# controller.net
KiCad netlist of a schematic drawn in EAGLE
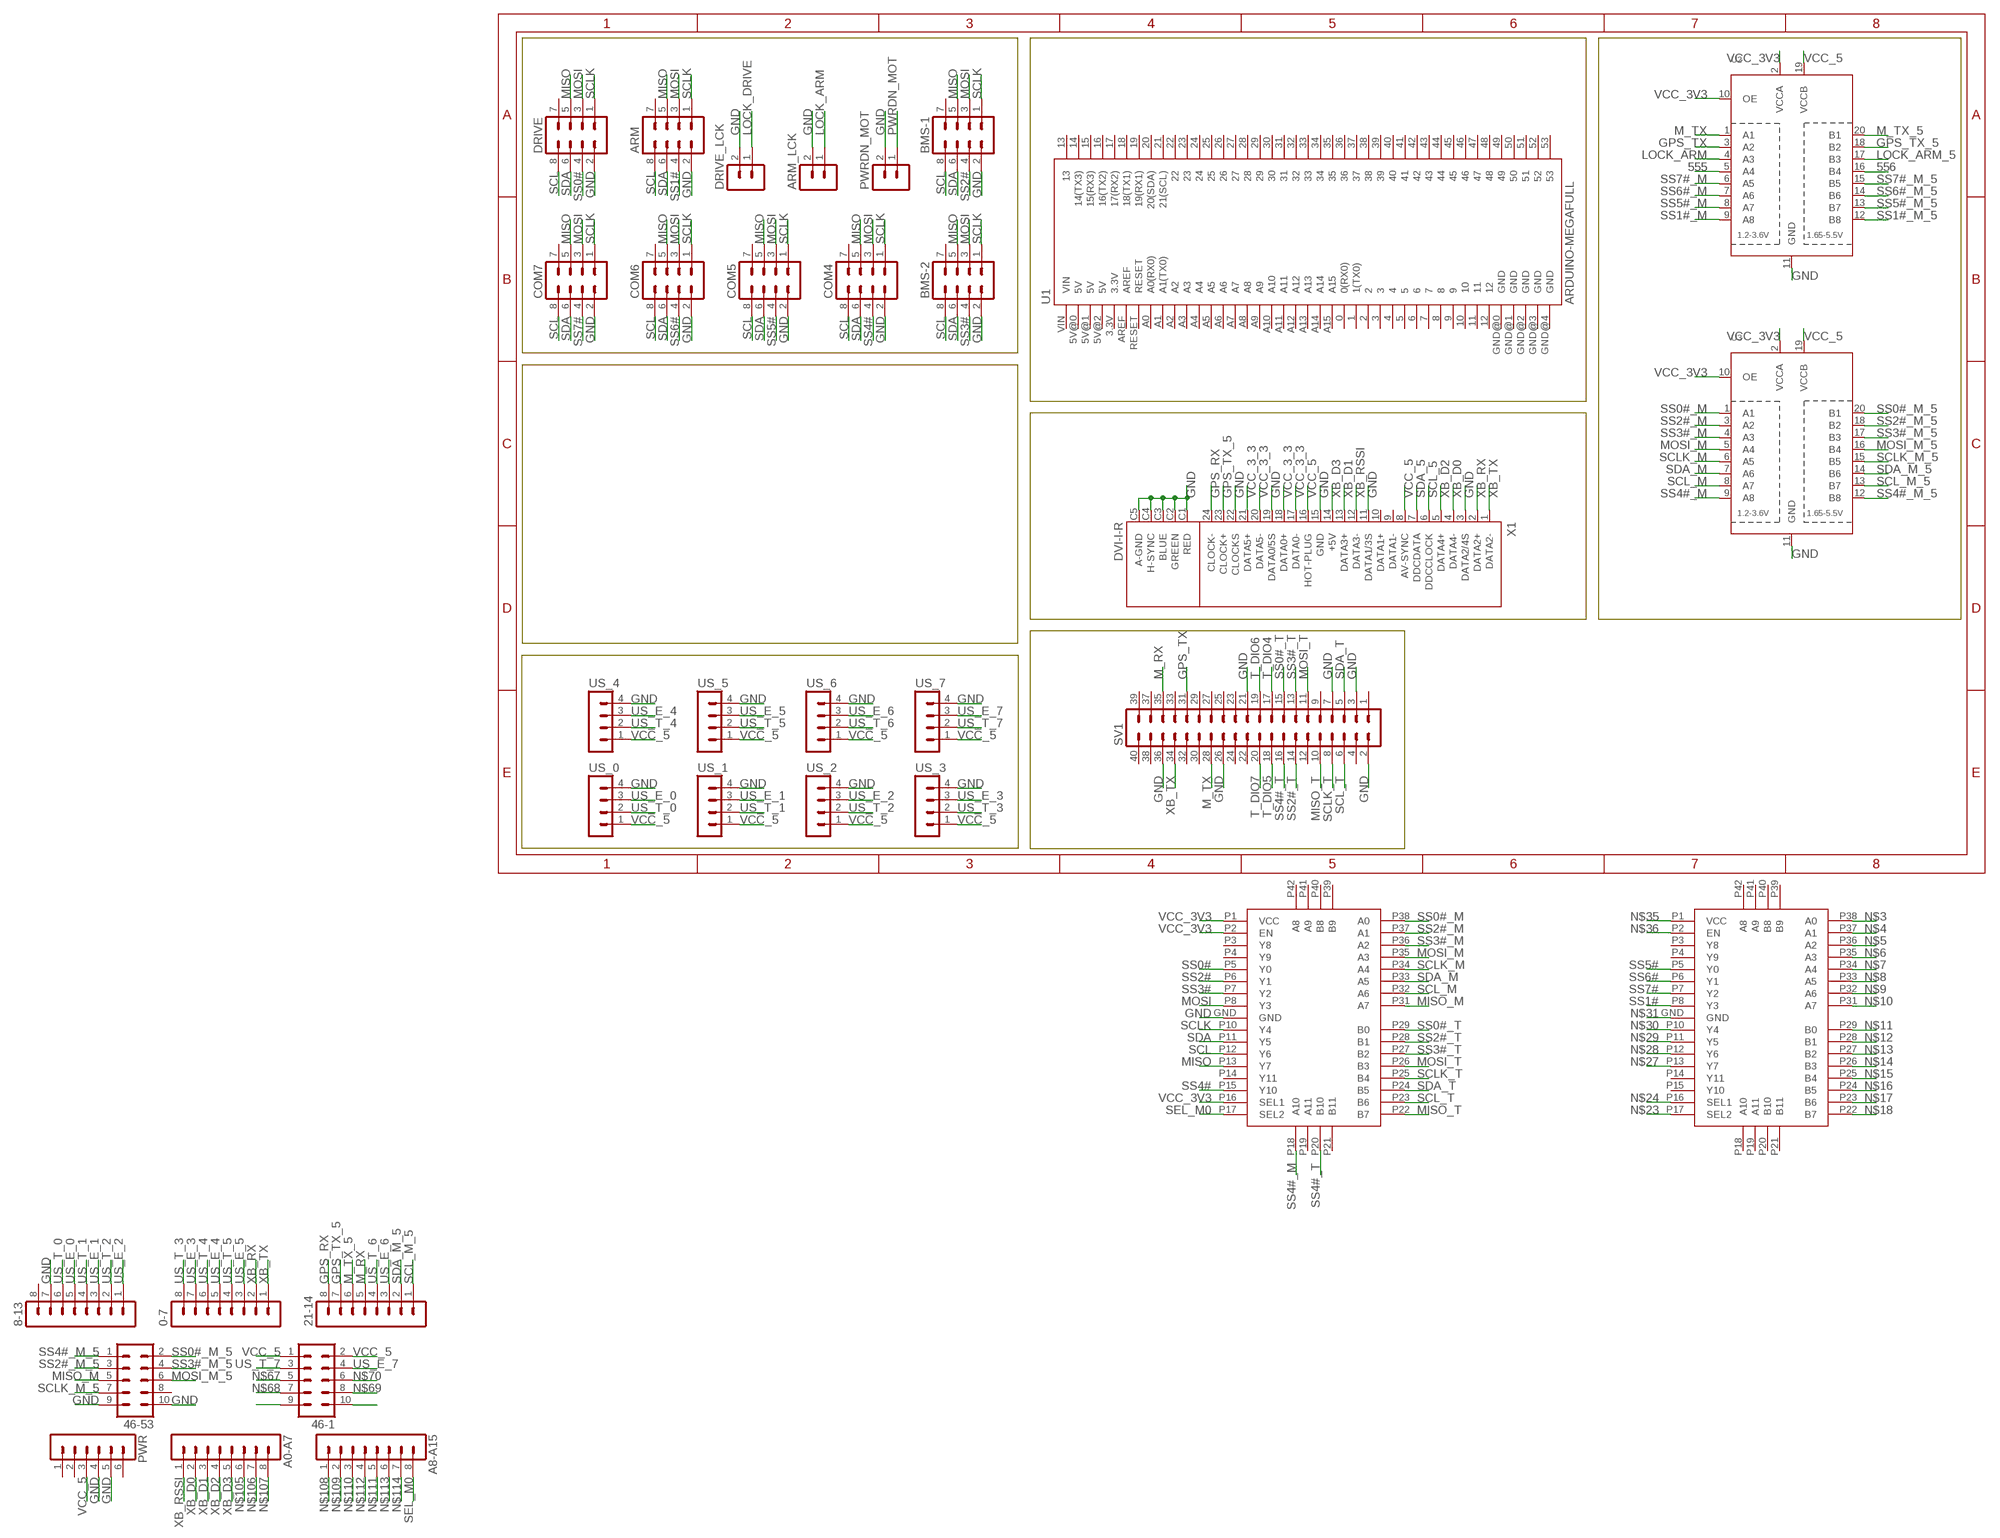
[diagram p0: schematic, sheet 1]

(export (version "E")
  (design (tool "Eeschema 10.0.6"))
  (components
    (comp (ref "0-7")
      (value "MA08-1")
      (footprint "eagle-import:MA08-1")
      (libsource (lib "eagle-import") (part "MA08-1"))
    )
    (comp (ref "8-13")
      (value "MA08-1")
      (footprint "eagle-import:MA08-1")
      (libsource (lib "eagle-import") (part "MA08-1"))
    )
    (comp (ref "21-14")
      (value "MA08-1")
      (footprint "eagle-import:MA08-1")
      (libsource (lib "eagle-import") (part "MA08-1"))
    )
    (comp (ref "46-1")
      (value "MA05-2")
      (footprint "eagle-import:MA05-2")
      (libsource (lib "eagle-import") (part "MA05-2"))
    )
    (comp (ref "46-53")
      (value "MA05-2")
      (footprint "eagle-import:MA05-2")
      (libsource (lib "eagle-import") (part "MA05-2"))
    )
    (comp (ref "A0-A7")
      (value "MA08-1")
      (footprint "eagle-import:MA08-1")
      (libsource (lib "eagle-import") (part "MA08-1"))
    )
    (comp (ref "A8-A15")
      (value "MA08-1")
      (footprint "eagle-import:MA08-1")
      (libsource (lib "eagle-import") (part "MA08-1"))
    )
    (comp (ref "ARM")
      (value "MA04-2")
      (footprint "eagle-import:MA04-2")
      (libsource (lib "eagle-import") (part "MA04-2"))
    )
    (comp (ref "ARM_LCK")
      (value "MA02-1")
      (footprint "eagle-import:MA02-1")
      (libsource (lib "eagle-import") (part "MA02-1"))
    )
    (comp (ref "BMS-1")
      (value "MA04-2")
      (footprint "eagle-import:MA04-2")
      (libsource (lib "eagle-import") (part "MA04-2"))
    )
    (comp (ref "BMS-2")
      (value "MA04-2")
      (footprint "eagle-import:MA04-2")
      (libsource (lib "eagle-import") (part "MA04-2"))
    )
    (comp (ref "COM4")
      (value "MA04-2")
      (footprint "eagle-import:MA04-2")
      (libsource (lib "eagle-import") (part "MA04-2"))
    )
    (comp (ref "COM5")
      (value "MA04-2")
      (footprint "eagle-import:MA04-2")
      (libsource (lib "eagle-import") (part "MA04-2"))
    )
    (comp (ref "COM6")
      (value "MA04-2")
      (footprint "eagle-import:MA04-2")
      (libsource (lib "eagle-import") (part "MA04-2"))
    )
    (comp (ref "COM7")
      (value "MA04-2")
      (footprint "eagle-import:MA04-2")
      (libsource (lib "eagle-import") (part "MA04-2"))
    )
    (comp (ref "DRIVE")
      (value "MA04-2")
      (footprint "eagle-import:MA04-2")
      (libsource (lib "eagle-import") (part "MA04-2"))
    )
    (comp (ref "DRIVE_LCK")
      (value "MA02-1")
      (footprint "eagle-import:MA02-1")
      (libsource (lib "eagle-import") (part "MA02-1"))
    )
    (comp (ref "PWR")
      (value "MA06-1")
      (footprint "eagle-import:MA06-1")
      (libsource (lib "eagle-import") (part "MA06-1"))
    )
    (comp (ref "PWRDN_MOT")
      (value "MA02-1")
      (footprint "eagle-import:MA02-1")
      (libsource (lib "eagle-import") (part "MA02-1"))
    )
    (comp (ref "SV1")
      (value "MA20-2")
      (footprint "eagle-import:MA20-2")
      (libsource (lib "eagle-import") (part "MA20-2"))
    )
    (comp (ref "U$5")
      (value "TS3DV642RUA")
      (footprint "eagle-import:R-PWQFN-N42")
      (libsource (lib "eagle-import") (part "TS3DV642RUA"))
    )
    (comp (ref "U$6")
      (value "TS3DV642RUA")
      (footprint "eagle-import:R-PWQFN-N42")
      (libsource (lib "eagle-import") (part "TS3DV642RUA"))
    )
    (comp (ref "U1")
      (value "ARDUINO-MEGAFULL")
      (footprint "eagle-import:ARDUINO_MEGA")
      (libsource (lib "eagle-import") (part "ARDUINO-MEGAFULL"))
    )
    (comp (ref "U2")
      (value "TXB0108PWR")
      (footprint "eagle-import:TSSOP20")
      (libsource (lib "eagle-import") (part "TXB0108PWR"))
    )
    (comp (ref "U3")
      (value "TXB0108PWR")
      (footprint "eagle-import:TSSOP20")
      (libsource (lib "eagle-import") (part "TXB0108PWR"))
    )
    (comp (ref "US_0")
      (value "MA04-1")
      (footprint "eagle-import:MA04-1")
      (libsource (lib "eagle-import") (part "MA04-1"))
    )
    (comp (ref "US_1")
      (value "MA04-1")
      (footprint "eagle-import:MA04-1")
      (libsource (lib "eagle-import") (part "MA04-1"))
    )
    (comp (ref "US_2")
      (value "MA04-1")
      (footprint "eagle-import:MA04-1")
      (libsource (lib "eagle-import") (part "MA04-1"))
    )
    (comp (ref "US_3")
      (value "MA04-1")
      (footprint "eagle-import:MA04-1")
      (libsource (lib "eagle-import") (part "MA04-1"))
    )
    (comp (ref "US_4")
      (value "MA04-1")
      (footprint "eagle-import:MA04-1")
      (libsource (lib "eagle-import") (part "MA04-1"))
    )
    (comp (ref "US_5")
      (value "MA04-1")
      (footprint "eagle-import:MA04-1")
      (libsource (lib "eagle-import") (part "MA04-1"))
    )
    (comp (ref "US_6")
      (value "MA04-1")
      (footprint "eagle-import:MA04-1")
      (libsource (lib "eagle-import") (part "MA04-1"))
    )
    (comp (ref "US_7")
      (value "MA04-1")
      (footprint "eagle-import:MA04-1")
      (libsource (lib "eagle-import") (part "MA04-1"))
    )
    (comp (ref "X1")
      (value "DVI-I-R")
      (footprint "eagle-import:DVI-I-R")
      (libsource (lib "eagle-import") (part "DVI-I-R"))
    )
  )
  (nets
    (net (code "1") (name "/555") (class "Default")
      (node (ref "U2") (pin "5") (pinfunction "A4_5") (pintype "bidirectional"))
    )
    (net (code "2") (name "/556") (class "Default")
      (node (ref "U2") (pin "16") (pinfunction "B4_16") (pintype "bidirectional"))
    )
    (net (code "3") (name "/GND") (class "Default")
      (node (ref "46-53") (pin "10") (pinfunction "10_10") (pintype "passive"))
      (node (ref "46-53") (pin "9") (pinfunction "9_9") (pintype "passive"))
      (node (ref "8-13") (pin "7") (pinfunction "7_7") (pintype "passive"))
      (node (ref "ARM") (pin "2") (pinfunction "2_2") (pintype "passive"))
      (node (ref "ARM_LCK") (pin "2") (pinfunction "2_2") (pintype "passive"))
      (node (ref "BMS-1") (pin "2") (pinfunction "2_2") (pintype "passive"))
      (node (ref "BMS-2") (pin "2") (pinfunction "2_2") (pintype "passive"))
      (node (ref "COM4") (pin "2") (pinfunction "2_2") (pintype "passive"))
      (node (ref "COM5") (pin "2") (pinfunction "2_2") (pintype "passive"))
      (node (ref "COM6") (pin "2") (pinfunction "2_2") (pintype "passive"))
      (node (ref "COM7") (pin "2") (pinfunction "2_2") (pintype "passive"))
      (node (ref "DRIVE") (pin "2") (pinfunction "2_2") (pintype "passive"))
      (node (ref "DRIVE_LCK") (pin "2") (pinfunction "2_2") (pintype "passive"))
      (node (ref "PWR") (pin "4") (pinfunction "4_4") (pintype "passive"))
      (node (ref "PWR") (pin "5") (pinfunction "5_5") (pintype "passive"))
      (node (ref "PWRDN_MOT") (pin "2") (pinfunction "2_2") (pintype "passive"))
      (node (ref "SV1") (pin "2") (pinfunction "2_2") (pintype "passive"))
      (node (ref "SV1") (pin "21") (pinfunction "21_21") (pintype "passive"))
      (node (ref "SV1") (pin "26") (pinfunction "26_26") (pintype "passive"))
      (node (ref "SV1") (pin "3") (pinfunction "3_3") (pintype "passive"))
      (node (ref "SV1") (pin "36") (pinfunction "36_36") (pintype "passive"))
      (node (ref "SV1") (pin "7") (pinfunction "7_7") (pintype "passive"))
      (node (ref "U$5") (pin "GND") (pinfunction "GND_GND") (pintype "bidirectional"))
      (node (ref "U2") (pin "11") (pinfunction "GND_11") (pintype "bidirectional"))
      (node (ref "U3") (pin "11") (pinfunction "GND_11") (pintype "bidirectional"))
      (node (ref "US_0") (pin "4") (pinfunction "4_4") (pintype "passive"))
      (node (ref "US_1") (pin "4") (pinfunction "4_4") (pintype "passive"))
      (node (ref "US_2") (pin "4") (pinfunction "4_4") (pintype "passive"))
      (node (ref "US_3") (pin "4") (pinfunction "4_4") (pintype "passive"))
      (node (ref "US_4") (pin "4") (pinfunction "4_4") (pintype "passive"))
      (node (ref "US_5") (pin "4") (pinfunction "4_4") (pintype "passive"))
      (node (ref "US_6") (pin "4") (pinfunction "4_4") (pintype "passive"))
      (node (ref "US_7") (pin "4") (pinfunction "4_4") (pintype "passive"))
      (node (ref "X1") (pin "11") (pinfunction "DATA1/3S_11") (pintype "passive"))
      (node (ref "X1") (pin "15") (pinfunction "GND_15") (pintype "power_in"))
      (node (ref "X1") (pin "19") (pinfunction "DATA0/5S_19") (pintype "passive"))
      (node (ref "X1") (pin "22") (pinfunction "CLOCKS_22") (pintype "passive"))
      (node (ref "X1") (pin "3") (pinfunction "DATA2/4S_3") (pintype "passive"))
      (node (ref "X1") (pin "C1") (pinfunction "RED_C1") (pintype "passive"))
      (node (ref "X1") (pin "C2") (pinfunction "GREEN_C2") (pintype "passive"))
      (node (ref "X1") (pin "C3") (pinfunction "BLUE_C3") (pintype "passive"))
      (node (ref "X1") (pin "C4") (pinfunction "H-SYNC_C4") (pintype "passive"))
      (node (ref "X1") (pin "C5") (pinfunction "A-GND_C5") (pintype "power_in"))
    )
    (net (code "4") (name "/GPS_RX") (class "Default")
      (node (ref "21-14") (pin "8") (pinfunction "8_8") (pintype "passive"))
      (node (ref "X1") (pin "24") (pinfunction "CLOCK-_24") (pintype "passive"))
    )
    (net (code "5") (name "/GPS_TX") (class "Default")
      (node (ref "SV1") (pin "31") (pinfunction "31_31") (pintype "passive"))
      (node (ref "U2") (pin "3") (pinfunction "A2_3") (pintype "bidirectional"))
    )
    (net (code "6") (name "/GPS_TX_5") (class "Default")
      (node (ref "21-14") (pin "7") (pinfunction "7_7") (pintype "passive"))
      (node (ref "U2") (pin "18") (pinfunction "B2_18") (pintype "bidirectional"))
      (node (ref "X1") (pin "23") (pinfunction "CLOCK+_23") (pintype "passive"))
    )
    (net (code "7") (name "/LOCK_ARM") (class "Default")
      (node (ref "ARM_LCK") (pin "1") (pinfunction "1_1") (pintype "passive"))
      (node (ref "U2") (pin "4") (pinfunction "A3_4") (pintype "bidirectional"))
    )
    (net (code "8") (name "/LOCK_ARM_5") (class "Default")
      (node (ref "U2") (pin "17") (pinfunction "B3_17") (pintype "bidirectional"))
    )
    (net (code "9") (name "/LOCK_DRIVE") (class "Default")
      (node (ref "DRIVE_LCK") (pin "1") (pinfunction "1_1") (pintype "passive"))
    )
    (net (code "10") (name "/MISO") (class "Default")
      (node (ref "ARM") (pin "5") (pinfunction "5_5") (pintype "passive"))
      (node (ref "BMS-1") (pin "5") (pinfunction "5_5") (pintype "passive"))
      (node (ref "BMS-2") (pin "5") (pinfunction "5_5") (pintype "passive"))
      (node (ref "COM4") (pin "5") (pinfunction "5_5") (pintype "passive"))
      (node (ref "COM5") (pin "5") (pinfunction "5_5") (pintype "passive"))
      (node (ref "COM6") (pin "5") (pinfunction "5_5") (pintype "passive"))
      (node (ref "COM7") (pin "5") (pinfunction "5_5") (pintype "passive"))
      (node (ref "DRIVE") (pin "5") (pinfunction "5_5") (pintype "passive"))
      (node (ref "U$5") (pin "P13") (pinfunction "Y7_P13") (pintype "bidirectional"))
    )
    (net (code "11") (name "/MISO_M") (class "Default")
      (node (ref "46-53") (pin "5") (pinfunction "5_5") (pintype "passive"))
      (node (ref "U$5") (pin "P31") (pinfunction "A7_P31") (pintype "bidirectional"))
    )
    (net (code "12") (name "/MISO_T") (class "Default")
      (node (ref "SV1") (pin "10") (pinfunction "10_10") (pintype "passive"))
      (node (ref "U$5") (pin "P22") (pinfunction "B7_P22") (pintype "bidirectional"))
    )
    (net (code "13") (name "/MOSI") (class "Default")
      (node (ref "ARM") (pin "3") (pinfunction "3_3") (pintype "passive"))
      (node (ref "BMS-1") (pin "3") (pinfunction "3_3") (pintype "passive"))
      (node (ref "BMS-2") (pin "3") (pinfunction "3_3") (pintype "passive"))
      (node (ref "COM4") (pin "3") (pinfunction "3_3") (pintype "passive"))
      (node (ref "COM5") (pin "3") (pinfunction "3_3") (pintype "passive"))
      (node (ref "COM6") (pin "3") (pinfunction "3_3") (pintype "passive"))
      (node (ref "COM7") (pin "3") (pinfunction "3_3") (pintype "passive"))
      (node (ref "DRIVE") (pin "3") (pinfunction "3_3") (pintype "passive"))
      (node (ref "U$5") (pin "P8") (pinfunction "Y3_P8") (pintype "bidirectional"))
    )
    (net (code "14") (name "/MOSI_M") (class "Default")
      (node (ref "U$5") (pin "P35") (pinfunction "A3_P35") (pintype "bidirectional"))
      (node (ref "U3") (pin "5") (pinfunction "A4_5") (pintype "bidirectional"))
    )
    (net (code "15") (name "/MOSI_M_5") (class "Default")
      (node (ref "46-53") (pin "6") (pinfunction "6_6") (pintype "passive"))
      (node (ref "U3") (pin "16") (pinfunction "B4_16") (pintype "bidirectional"))
    )
    (net (code "16") (name "/MOSI_T") (class "Default")
      (node (ref "SV1") (pin "11") (pinfunction "11_11") (pintype "passive"))
      (node (ref "U$5") (pin "P26") (pinfunction "B3_P26") (pintype "bidirectional"))
    )
    (net (code "17") (name "/M_RX") (class "Default")
      (node (ref "21-14") (pin "5") (pinfunction "5_5") (pintype "passive"))
      (node (ref "SV1") (pin "35") (pinfunction "35_35") (pintype "passive"))
    )
    (net (code "18") (name "/M_TX") (class "Default")
      (node (ref "SV1") (pin "28") (pinfunction "28_28") (pintype "passive"))
      (node (ref "U2") (pin "1") (pinfunction "A1_1") (pintype "bidirectional"))
    )
    (net (code "19") (name "/M_TX_5") (class "Default")
      (node (ref "21-14") (pin "6") (pinfunction "6_6") (pintype "passive"))
      (node (ref "U2") (pin "20") (pinfunction "B1_20") (pintype "bidirectional"))
    )
    (net (code "20") (name "/N$3") (class "Default")
      (node (ref "U$6") (pin "P38") (pinfunction "A0_P38") (pintype "bidirectional"))
    )
    (net (code "21") (name "/N$4") (class "Default")
      (node (ref "U$6") (pin "P37") (pinfunction "A1_P37") (pintype "bidirectional"))
    )
    (net (code "22") (name "/N$5") (class "Default")
      (node (ref "U$6") (pin "P36") (pinfunction "A2_P36") (pintype "bidirectional"))
    )
    (net (code "23") (name "/N$6") (class "Default")
      (node (ref "U$6") (pin "P35") (pinfunction "A3_P35") (pintype "bidirectional"))
    )
    (net (code "24") (name "/N$7") (class "Default")
      (node (ref "U$6") (pin "P34") (pinfunction "A4_P34") (pintype "bidirectional"))
    )
    (net (code "25") (name "/N$8") (class "Default")
      (node (ref "U$6") (pin "P33") (pinfunction "A5_P33") (pintype "bidirectional"))
    )
    (net (code "26") (name "/N$9") (class "Default")
      (node (ref "U$6") (pin "P32") (pinfunction "A6_P32") (pintype "bidirectional"))
    )
    (net (code "27") (name "/N$10") (class "Default")
      (node (ref "U$6") (pin "P31") (pinfunction "A7_P31") (pintype "bidirectional"))
    )
    (net (code "28") (name "/N$11") (class "Default")
      (node (ref "U$6") (pin "P29") (pinfunction "B0_P29") (pintype "bidirectional"))
    )
    (net (code "29") (name "/N$12") (class "Default")
      (node (ref "U$6") (pin "P28") (pinfunction "B1_P28") (pintype "bidirectional"))
    )
    (net (code "30") (name "/N$13") (class "Default")
      (node (ref "U$6") (pin "P27") (pinfunction "B2_P27") (pintype "bidirectional"))
    )
    (net (code "31") (name "/N$14") (class "Default")
      (node (ref "U$6") (pin "P26") (pinfunction "B3_P26") (pintype "bidirectional"))
    )
    (net (code "32") (name "/N$15") (class "Default")
      (node (ref "U$6") (pin "P25") (pinfunction "B4_P25") (pintype "bidirectional"))
    )
    (net (code "33") (name "/N$16") (class "Default")
      (node (ref "U$6") (pin "P24") (pinfunction "B5_P24") (pintype "bidirectional"))
    )
    (net (code "34") (name "/N$17") (class "Default")
      (node (ref "U$6") (pin "P23") (pinfunction "B6_P23") (pintype "bidirectional"))
    )
    (net (code "35") (name "/N$18") (class "Default")
      (node (ref "U$6") (pin "P22") (pinfunction "B7_P22") (pintype "bidirectional"))
    )
    (net (code "36") (name "/N$23") (class "Default")
      (node (ref "U$6") (pin "P17") (pinfunction "SEL2_P17") (pintype "bidirectional"))
    )
    (net (code "37") (name "/N$24") (class "Default")
      (node (ref "U$6") (pin "P16") (pinfunction "SEL1_P16") (pintype "bidirectional"))
    )
    (net (code "38") (name "/N$27") (class "Default")
      (node (ref "U$6") (pin "P13") (pinfunction "Y7_P13") (pintype "bidirectional"))
    )
    (net (code "39") (name "/N$28") (class "Default")
      (node (ref "U$6") (pin "P12") (pinfunction "Y6_P12") (pintype "bidirectional"))
    )
    (net (code "40") (name "/N$29") (class "Default")
      (node (ref "U$6") (pin "P11") (pinfunction "Y5_P11") (pintype "bidirectional"))
    )
    (net (code "41") (name "/N$30") (class "Default")
      (node (ref "U$6") (pin "P10") (pinfunction "Y4_P10") (pintype "bidirectional"))
    )
    (net (code "42") (name "/N$31") (class "Default")
      (node (ref "U$6") (pin "GND") (pinfunction "GND_GND") (pintype "bidirectional"))
    )
    (net (code "43") (name "/N$35") (class "Default")
      (node (ref "U$6") (pin "P1") (pinfunction "VCC_P1") (pintype "bidirectional"))
    )
    (net (code "44") (name "/N$36") (class "Default")
      (node (ref "U$6") (pin "P2") (pinfunction "EN_P2") (pintype "bidirectional"))
    )
    (net (code "45") (name "/N$67") (class "Default")
      (node (ref "46-1") (pin "5") (pinfunction "5_5") (pintype "passive"))
    )
    (net (code "46") (name "/N$68") (class "Default")
      (node (ref "46-1") (pin "7") (pinfunction "7_7") (pintype "passive"))
    )
    (net (code "47") (name "/N$69") (class "Default")
      (node (ref "46-1") (pin "8") (pinfunction "8_8") (pintype "passive"))
    )
    (net (code "48") (name "/N$70") (class "Default")
      (node (ref "46-1") (pin "6") (pinfunction "6_6") (pintype "passive"))
    )
    (net (code "49") (name "/N$105") (class "Default")
      (node (ref "A0-A7") (pin "6") (pinfunction "6_6") (pintype "passive"))
    )
    (net (code "50") (name "/N$106") (class "Default")
      (node (ref "A0-A7") (pin "7") (pinfunction "7_7") (pintype "passive"))
    )
    (net (code "51") (name "/N$107") (class "Default")
      (node (ref "A0-A7") (pin "8") (pinfunction "8_8") (pintype "passive"))
    )
    (net (code "52") (name "/N$108") (class "Default")
      (node (ref "A8-A15") (pin "1") (pinfunction "1_1") (pintype "passive"))
    )
    (net (code "53") (name "/N$109") (class "Default")
      (node (ref "A8-A15") (pin "2") (pinfunction "2_2") (pintype "passive"))
    )
    (net (code "54") (name "/N$110") (class "Default")
      (node (ref "A8-A15") (pin "3") (pinfunction "3_3") (pintype "passive"))
    )
    (net (code "55") (name "/N$111") (class "Default")
      (node (ref "A8-A15") (pin "5") (pinfunction "5_5") (pintype "passive"))
    )
    (net (code "56") (name "/N$112") (class "Default")
      (node (ref "A8-A15") (pin "4") (pinfunction "4_4") (pintype "passive"))
    )
    (net (code "57") (name "/N$113") (class "Default")
      (node (ref "A8-A15") (pin "6") (pinfunction "6_6") (pintype "passive"))
    )
    (net (code "58") (name "/N$114") (class "Default")
      (node (ref "A8-A15") (pin "7") (pinfunction "7_7") (pintype "passive"))
    )
    (net (code "59") (name "/PWRDN_MOT") (class "Default")
      (node (ref "PWRDN_MOT") (pin "1") (pinfunction "1_1") (pintype "passive"))
    )
    (net (code "60") (name "/SCL") (class "Default")
      (node (ref "ARM") (pin "8") (pinfunction "8_8") (pintype "passive"))
      (node (ref "BMS-1") (pin "8") (pinfunction "8_8") (pintype "passive"))
      (node (ref "BMS-2") (pin "8") (pinfunction "8_8") (pintype "passive"))
      (node (ref "COM4") (pin "8") (pinfunction "8_8") (pintype "passive"))
      (node (ref "COM5") (pin "8") (pinfunction "8_8") (pintype "passive"))
      (node (ref "COM6") (pin "8") (pinfunction "8_8") (pintype "passive"))
      (node (ref "COM7") (pin "8") (pinfunction "8_8") (pintype "passive"))
      (node (ref "DRIVE") (pin "8") (pinfunction "8_8") (pintype "passive"))
      (node (ref "U$5") (pin "P12") (pinfunction "Y6_P12") (pintype "bidirectional"))
    )
    (net (code "61") (name "/SCLK") (class "Default")
      (node (ref "ARM") (pin "1") (pinfunction "1_1") (pintype "passive"))
      (node (ref "BMS-1") (pin "1") (pinfunction "1_1") (pintype "passive"))
      (node (ref "BMS-2") (pin "1") (pinfunction "1_1") (pintype "passive"))
      (node (ref "COM4") (pin "1") (pinfunction "1_1") (pintype "passive"))
      (node (ref "COM5") (pin "1") (pinfunction "1_1") (pintype "passive"))
      (node (ref "COM6") (pin "1") (pinfunction "1_1") (pintype "passive"))
      (node (ref "COM7") (pin "1") (pinfunction "1_1") (pintype "passive"))
      (node (ref "DRIVE") (pin "1") (pinfunction "1_1") (pintype "passive"))
      (node (ref "U$5") (pin "P10") (pinfunction "Y4_P10") (pintype "bidirectional"))
    )
    (net (code "62") (name "/SCLK_M") (class "Default")
      (node (ref "U$5") (pin "P34") (pinfunction "A4_P34") (pintype "bidirectional"))
      (node (ref "U3") (pin "6") (pinfunction "A5_6") (pintype "bidirectional"))
    )
    (net (code "63") (name "/SCLK_M_5") (class "Default")
      (node (ref "46-53") (pin "7") (pinfunction "7_7") (pintype "passive"))
      (node (ref "U3") (pin "15") (pinfunction "B5_15") (pintype "bidirectional"))
    )
    (net (code "64") (name "/SCLK_T") (class "Default")
      (node (ref "SV1") (pin "8") (pinfunction "8_8") (pintype "passive"))
      (node (ref "U$5") (pin "P25") (pinfunction "B4_P25") (pintype "bidirectional"))
    )
    (net (code "65") (name "/SCL_5") (class "Default")
      (node (ref "X1") (pin "6") (pinfunction "DDCCLOCK_6") (pintype "passive"))
    )
    (net (code "66") (name "/SCL_M") (class "Default")
      (node (ref "U$5") (pin "P32") (pinfunction "A6_P32") (pintype "bidirectional"))
      (node (ref "U3") (pin "8") (pinfunction "A7_8") (pintype "bidirectional"))
    )
    (net (code "67") (name "/SCL_M_5") (class "Default")
      (node (ref "21-14") (pin "1") (pinfunction "1_1") (pintype "passive"))
      (node (ref "U3") (pin "13") (pinfunction "B7_13") (pintype "bidirectional"))
    )
    (net (code "68") (name "/SCL_T") (class "Default")
      (node (ref "SV1") (pin "6") (pinfunction "6_6") (pintype "passive"))
      (node (ref "U$5") (pin "P23") (pinfunction "B6_P23") (pintype "bidirectional"))
    )
    (net (code "69") (name "/SDA") (class "Default")
      (node (ref "ARM") (pin "6") (pinfunction "6_6") (pintype "passive"))
      (node (ref "BMS-1") (pin "6") (pinfunction "6_6") (pintype "passive"))
      (node (ref "BMS-2") (pin "6") (pinfunction "6_6") (pintype "passive"))
      (node (ref "COM4") (pin "6") (pinfunction "6_6") (pintype "passive"))
      (node (ref "COM5") (pin "6") (pinfunction "6_6") (pintype "passive"))
      (node (ref "COM6") (pin "6") (pinfunction "6_6") (pintype "passive"))
      (node (ref "COM7") (pin "6") (pinfunction "6_6") (pintype "passive"))
      (node (ref "DRIVE") (pin "6") (pinfunction "6_6") (pintype "passive"))
      (node (ref "U$5") (pin "P11") (pinfunction "Y5_P11") (pintype "bidirectional"))
    )
    (net (code "70") (name "/SDA_5") (class "Default")
      (node (ref "X1") (pin "7") (pinfunction "DDCDATA_7") (pintype "passive"))
    )
    (net (code "71") (name "/SDA_M") (class "Default")
      (node (ref "U$5") (pin "P33") (pinfunction "A5_P33") (pintype "bidirectional"))
      (node (ref "U3") (pin "7") (pinfunction "A6_7") (pintype "bidirectional"))
    )
    (net (code "72") (name "/SDA_M_5") (class "Default")
      (node (ref "21-14") (pin "2") (pinfunction "2_2") (pintype "passive"))
      (node (ref "U3") (pin "14") (pinfunction "B6_14") (pintype "bidirectional"))
    )
    (net (code "73") (name "/SDA_T") (class "Default")
      (node (ref "SV1") (pin "5") (pinfunction "5_5") (pintype "passive"))
      (node (ref "U$5") (pin "P24") (pinfunction "B5_P24") (pintype "bidirectional"))
    )
    (net (code "74") (name "/SEL_M0") (class "Default")
      (node (ref "A8-A15") (pin "8") (pinfunction "8_8") (pintype "passive"))
      (node (ref "U$5") (pin "P17") (pinfunction "SEL2_P17") (pintype "bidirectional"))
    )
    (net (code "75") (name "/SS0#") (class "Default")
      (node (ref "DRIVE") (pin "4") (pinfunction "4_4") (pintype "passive"))
      (node (ref "U$5") (pin "P5") (pinfunction "Y0_P5") (pintype "bidirectional"))
    )
    (net (code "76") (name "/SS0#_M") (class "Default")
      (node (ref "U$5") (pin "P38") (pinfunction "A0_P38") (pintype "bidirectional"))
      (node (ref "U3") (pin "1") (pinfunction "A1_1") (pintype "bidirectional"))
    )
    (net (code "77") (name "/SS0#_M_5") (class "Default")
      (node (ref "46-53") (pin "2") (pinfunction "2_2") (pintype "passive"))
      (node (ref "U3") (pin "20") (pinfunction "B1_20") (pintype "bidirectional"))
    )
    (net (code "78") (name "/SS0#_T") (class "Default")
      (node (ref "SV1") (pin "15") (pinfunction "15_15") (pintype "passive"))
      (node (ref "U$5") (pin "P29") (pinfunction "B0_P29") (pintype "bidirectional"))
    )
    (net (code "79") (name "/SS1#") (class "Default")
      (node (ref "ARM") (pin "4") (pinfunction "4_4") (pintype "passive"))
      (node (ref "U$6") (pin "P8") (pinfunction "Y3_P8") (pintype "bidirectional"))
    )
    (net (code "80") (name "/SS1#_M") (class "Default")
      (node (ref "U2") (pin "9") (pinfunction "A8_9") (pintype "bidirectional"))
    )
    (net (code "81") (name "/SS1#_M_5") (class "Default")
      (node (ref "U2") (pin "12") (pinfunction "B8_12") (pintype "bidirectional"))
    )
    (net (code "82") (name "/SS2#") (class "Default")
      (node (ref "BMS-1") (pin "4") (pinfunction "4_4") (pintype "passive"))
      (node (ref "U$5") (pin "P6") (pinfunction "Y1_P6") (pintype "bidirectional"))
    )
    (net (code "83") (name "/SS2#_M") (class "Default")
      (node (ref "U$5") (pin "P37") (pinfunction "A1_P37") (pintype "bidirectional"))
      (node (ref "U3") (pin "3") (pinfunction "A2_3") (pintype "bidirectional"))
    )
    (net (code "84") (name "/SS2#_M_5") (class "Default")
      (node (ref "46-53") (pin "3") (pinfunction "3_3") (pintype "passive"))
      (node (ref "U3") (pin "18") (pinfunction "B2_18") (pintype "bidirectional"))
    )
    (net (code "85") (name "/SS2#_T") (class "Default")
      (node (ref "SV1") (pin "14") (pinfunction "14_14") (pintype "passive"))
      (node (ref "U$5") (pin "P28") (pinfunction "B1_P28") (pintype "bidirectional"))
    )
    (net (code "86") (name "/SS3#") (class "Default")
      (node (ref "BMS-2") (pin "4") (pinfunction "4_4") (pintype "passive"))
      (node (ref "U$5") (pin "P7") (pinfunction "Y2_P7") (pintype "bidirectional"))
    )
    (net (code "87") (name "/SS3#_M") (class "Default")
      (node (ref "U$5") (pin "P36") (pinfunction "A2_P36") (pintype "bidirectional"))
      (node (ref "U3") (pin "4") (pinfunction "A3_4") (pintype "bidirectional"))
    )
    (net (code "88") (name "/SS3#_M_5") (class "Default")
      (node (ref "46-53") (pin "4") (pinfunction "4_4") (pintype "passive"))
      (node (ref "U3") (pin "17") (pinfunction "B3_17") (pintype "bidirectional"))
    )
    (net (code "89") (name "/SS3#_T") (class "Default")
      (node (ref "SV1") (pin "13") (pinfunction "13_13") (pintype "passive"))
      (node (ref "U$5") (pin "P27") (pinfunction "B2_P27") (pintype "bidirectional"))
    )
    (net (code "90") (name "/SS4#") (class "Default")
      (node (ref "COM4") (pin "4") (pinfunction "4_4") (pintype "passive"))
      (node (ref "U$5") (pin "P15") (pinfunction "Y10_P15") (pintype "bidirectional"))
    )
    (net (code "91") (name "/SS4#_M") (class "Default")
      (node (ref "U$5") (pin "P18") (pinfunction "A10_P18") (pintype "bidirectional"))
      (node (ref "U3") (pin "9") (pinfunction "A8_9") (pintype "bidirectional"))
    )
    (net (code "92") (name "/SS4#_M_5") (class "Default")
      (node (ref "46-53") (pin "1") (pinfunction "1_1") (pintype "passive"))
      (node (ref "U3") (pin "12") (pinfunction "B8_12") (pintype "bidirectional"))
    )
    (net (code "93") (name "/SS4#_T") (class "Default")
      (node (ref "SV1") (pin "16") (pinfunction "16_16") (pintype "passive"))
      (node (ref "U$5") (pin "P20") (pinfunction "B10_P20") (pintype "bidirectional"))
    )
    (net (code "94") (name "/SS5#") (class "Default")
      (node (ref "COM5") (pin "4") (pinfunction "4_4") (pintype "passive"))
      (node (ref "U$6") (pin "P5") (pinfunction "Y0_P5") (pintype "bidirectional"))
    )
    (net (code "95") (name "/SS5#_M") (class "Default")
      (node (ref "U2") (pin "8") (pinfunction "A7_8") (pintype "bidirectional"))
    )
    (net (code "96") (name "/SS5#_M_5") (class "Default")
      (node (ref "U2") (pin "13") (pinfunction "B7_13") (pintype "bidirectional"))
    )
    (net (code "97") (name "/SS6#") (class "Default")
      (node (ref "COM6") (pin "4") (pinfunction "4_4") (pintype "passive"))
      (node (ref "U$6") (pin "P6") (pinfunction "Y1_P6") (pintype "bidirectional"))
    )
    (net (code "98") (name "/SS6#_M") (class "Default")
      (node (ref "U2") (pin "7") (pinfunction "A6_7") (pintype "bidirectional"))
    )
    (net (code "99") (name "/SS6#_M_5") (class "Default")
      (node (ref "U2") (pin "14") (pinfunction "B6_14") (pintype "bidirectional"))
    )
    (net (code "100") (name "/SS7#") (class "Default")
      (node (ref "COM7") (pin "4") (pinfunction "4_4") (pintype "passive"))
      (node (ref "U$6") (pin "P7") (pinfunction "Y2_P7") (pintype "bidirectional"))
    )
    (net (code "101") (name "/SS7#_M") (class "Default")
      (node (ref "U2") (pin "6") (pinfunction "A5_6") (pintype "bidirectional"))
    )
    (net (code "102") (name "/SS7#_M_5") (class "Default")
      (node (ref "U2") (pin "15") (pinfunction "B5_15") (pintype "bidirectional"))
    )
    (net (code "103") (name "/T_DIO4") (class "Default")
      (node (ref "SV1") (pin "17") (pinfunction "17_17") (pintype "passive"))
    )
    (net (code "104") (name "/T_DIO5") (class "Default")
      (node (ref "SV1") (pin "18") (pinfunction "18_18") (pintype "passive"))
    )
    (net (code "105") (name "/T_DIO6") (class "Default")
      (node (ref "SV1") (pin "19") (pinfunction "19_19") (pintype "passive"))
    )
    (net (code "106") (name "/T_DIO7") (class "Default")
      (node (ref "SV1") (pin "20") (pinfunction "20_20") (pintype "passive"))
    )
    (net (code "107") (name "/US_E_0") (class "Default")
      (node (ref "8-13") (pin "5") (pinfunction "5_5") (pintype "passive"))
      (node (ref "US_0") (pin "3") (pinfunction "3_3") (pintype "passive"))
    )
    (net (code "108") (name "/US_E_1") (class "Default")
      (node (ref "8-13") (pin "3") (pinfunction "3_3") (pintype "passive"))
      (node (ref "US_1") (pin "3") (pinfunction "3_3") (pintype "passive"))
    )
    (net (code "109") (name "/US_E_2") (class "Default")
      (node (ref "8-13") (pin "1") (pinfunction "1_1") (pintype "passive"))
      (node (ref "US_2") (pin "3") (pinfunction "3_3") (pintype "passive"))
    )
    (net (code "110") (name "/US_E_3") (class "Default")
      (node (ref "0-7") (pin "7") (pinfunction "7_7") (pintype "passive"))
      (node (ref "US_3") (pin "3") (pinfunction "3_3") (pintype "passive"))
    )
    (net (code "111") (name "/US_E_4") (class "Default")
      (node (ref "0-7") (pin "5") (pinfunction "5_5") (pintype "passive"))
      (node (ref "US_4") (pin "3") (pinfunction "3_3") (pintype "passive"))
    )
    (net (code "112") (name "/US_E_5") (class "Default")
      (node (ref "0-7") (pin "3") (pinfunction "3_3") (pintype "passive"))
      (node (ref "US_5") (pin "3") (pinfunction "3_3") (pintype "passive"))
    )
    (net (code "113") (name "/US_E_6") (class "Default")
      (node (ref "21-14") (pin "3") (pinfunction "3_3") (pintype "passive"))
      (node (ref "US_6") (pin "3") (pinfunction "3_3") (pintype "passive"))
    )
    (net (code "114") (name "/US_E_7") (class "Default")
      (node (ref "46-1") (pin "4") (pinfunction "4_4") (pintype "passive"))
      (node (ref "US_7") (pin "3") (pinfunction "3_3") (pintype "passive"))
    )
    (net (code "115") (name "/US_T_0") (class "Default")
      (node (ref "8-13") (pin "6") (pinfunction "6_6") (pintype "passive"))
      (node (ref "US_0") (pin "2") (pinfunction "2_2") (pintype "passive"))
    )
    (net (code "116") (name "/US_T_1") (class "Default")
      (node (ref "8-13") (pin "4") (pinfunction "4_4") (pintype "passive"))
      (node (ref "US_1") (pin "2") (pinfunction "2_2") (pintype "passive"))
    )
    (net (code "117") (name "/US_T_2") (class "Default")
      (node (ref "8-13") (pin "2") (pinfunction "2_2") (pintype "passive"))
      (node (ref "US_2") (pin "2") (pinfunction "2_2") (pintype "passive"))
    )
    (net (code "118") (name "/US_T_3") (class "Default")
      (node (ref "0-7") (pin "8") (pinfunction "8_8") (pintype "passive"))
      (node (ref "US_3") (pin "2") (pinfunction "2_2") (pintype "passive"))
    )
    (net (code "119") (name "/US_T_4") (class "Default")
      (node (ref "0-7") (pin "6") (pinfunction "6_6") (pintype "passive"))
      (node (ref "US_4") (pin "2") (pinfunction "2_2") (pintype "passive"))
    )
    (net (code "120") (name "/US_T_5") (class "Default")
      (node (ref "0-7") (pin "4") (pinfunction "4_4") (pintype "passive"))
      (node (ref "US_5") (pin "2") (pinfunction "2_2") (pintype "passive"))
    )
    (net (code "121") (name "/US_T_6") (class "Default")
      (node (ref "21-14") (pin "4") (pinfunction "4_4") (pintype "passive"))
      (node (ref "US_6") (pin "2") (pinfunction "2_2") (pintype "passive"))
    )
    (net (code "122") (name "/US_T_7") (class "Default")
      (node (ref "46-1") (pin "3") (pinfunction "3_3") (pintype "passive"))
      (node (ref "US_7") (pin "2") (pinfunction "2_2") (pintype "passive"))
    )
    (net (code "123") (name "/VCC_3V3") (class "Default")
      (node (ref "U$5") (pin "P1") (pinfunction "VCC_P1") (pintype "bidirectional"))
      (node (ref "U$5") (pin "P16") (pinfunction "SEL1_P16") (pintype "bidirectional"))
      (node (ref "U$5") (pin "P2") (pinfunction "EN_P2") (pintype "bidirectional"))
      (node (ref "U2") (pin "10") (pinfunction "OE_10") (pintype "bidirectional"))
      (node (ref "U2") (pin "2") (pinfunction "VCCA_2") (pintype "bidirectional"))
      (node (ref "U3") (pin "10") (pinfunction "OE_10") (pintype "bidirectional"))
      (node (ref "U3") (pin "2") (pinfunction "VCCA_2") (pintype "bidirectional"))
    )
    (net (code "124") (name "/VCC_3_3") (class "Default")
      (node (ref "X1") (pin "17") (pinfunction "DATA0-_17") (pintype "passive"))
      (node (ref "X1") (pin "18") (pinfunction "DATA0+_18") (pintype "passive"))
      (node (ref "X1") (pin "20") (pinfunction "DATA5-_20") (pintype "passive"))
      (node (ref "X1") (pin "21") (pinfunction "DATA5+_21") (pintype "passive"))
    )
    (net (code "125") (name "/VCC_5") (class "Default")
      (node (ref "46-1") (pin "1") (pinfunction "1_1") (pintype "passive"))
      (node (ref "46-1") (pin "2") (pinfunction "2_2") (pintype "passive"))
      (node (ref "PWR") (pin "3") (pinfunction "3_3") (pintype "passive"))
      (node (ref "U2") (pin "19") (pinfunction "VCCB_19") (pintype "bidirectional"))
      (node (ref "U3") (pin "19") (pinfunction "VCCB_19") (pintype "bidirectional"))
      (node (ref "US_0") (pin "1") (pinfunction "1_1") (pintype "passive"))
      (node (ref "US_1") (pin "1") (pinfunction "1_1") (pintype "passive"))
      (node (ref "US_2") (pin "1") (pinfunction "1_1") (pintype "passive"))
      (node (ref "US_3") (pin "1") (pinfunction "1_1") (pintype "passive"))
      (node (ref "US_4") (pin "1") (pinfunction "1_1") (pintype "passive"))
      (node (ref "US_5") (pin "1") (pinfunction "1_1") (pintype "passive"))
      (node (ref "US_6") (pin "1") (pinfunction "1_1") (pintype "passive"))
      (node (ref "US_7") (pin "1") (pinfunction "1_1") (pintype "passive"))
      (node (ref "X1") (pin "16") (pinfunction "HOT-PLUG_16") (pintype "passive"))
      (node (ref "X1") (pin "8") (pinfunction "AV-SYNC_8") (pintype "passive"))
    )
    (net (code "126") (name "/XB_D0") (class "Default")
      (node (ref "A0-A7") (pin "2") (pinfunction "2_2") (pintype "passive"))
      (node (ref "X1") (pin "4") (pinfunction "DATA4-_4") (pintype "passive"))
    )
    (net (code "127") (name "/XB_D1") (class "Default")
      (node (ref "A0-A7") (pin "3") (pinfunction "3_3") (pintype "passive"))
      (node (ref "X1") (pin "13") (pinfunction "DATA3+_13") (pintype "passive"))
    )
    (net (code "128") (name "/XB_D2") (class "Default")
      (node (ref "A0-A7") (pin "4") (pinfunction "4_4") (pintype "passive"))
      (node (ref "X1") (pin "5") (pinfunction "DATA4+_5") (pintype "passive"))
    )
    (net (code "129") (name "/XB_D3") (class "Default")
      (node (ref "A0-A7") (pin "5") (pinfunction "5_5") (pintype "passive"))
      (node (ref "X1") (pin "14") (pinfunction "+5V_14") (pintype "power_in"))
    )
    (net (code "130") (name "/XB_RSSI") (class "Default")
      (node (ref "A0-A7") (pin "1") (pinfunction "1_1") (pintype "passive"))
      (node (ref "X1") (pin "12") (pinfunction "DATA3-_12") (pintype "passive"))
    )
    (net (code "131") (name "/XB_RX") (class "Default")
      (node (ref "0-7") (pin "2") (pinfunction "2_2") (pintype "passive"))
      (node (ref "X1") (pin "2") (pinfunction "DATA2+_2") (pintype "passive"))
    )
    (net (code "132") (name "/XB_TX") (class "Default")
      (node (ref "0-7") (pin "1") (pinfunction "1_1") (pintype "passive"))
      (node (ref "SV1") (pin "34") (pinfunction "34_34") (pintype "passive"))
      (node (ref "X1") (pin "1") (pinfunction "DATA2-_1") (pintype "passive"))
    )
    (net (code "133") (name "unconnected-(8-13-Pad8)") (class "Default")
      (node (ref "8-13") (pin "8") (pinfunction "8_8") (pintype "passive"))
    )
    (net (code "134") (name "unconnected-(46-1-Pad9)") (class "Default")
      (node (ref "46-1") (pin "9") (pinfunction "9_9") (pintype "passive"))
    )
    (net (code "135") (name "unconnected-(46-1-Pad10)") (class "Default")
      (node (ref "46-1") (pin "10") (pinfunction "10_10") (pintype "passive"))
    )
    (net (code "136") (name "unconnected-(46-53-Pad8)") (class "Default")
      (node (ref "46-53") (pin "8") (pinfunction "8_8") (pintype "passive"))
    )
    (net (code "137") (name "unconnected-(ARM-Pad7)") (class "Default")
      (node (ref "ARM") (pin "7") (pinfunction "7_7") (pintype "passive"))
    )
    (net (code "138") (name "unconnected-(BMS-1-Pad7)") (class "Default")
      (node (ref "BMS-1") (pin "7") (pinfunction "7_7") (pintype "passive"))
    )
    (net (code "139") (name "unconnected-(BMS-2-Pad7)") (class "Default")
      (node (ref "BMS-2") (pin "7") (pinfunction "7_7") (pintype "passive"))
    )
    (net (code "140") (name "unconnected-(COM4-Pad7)") (class "Default")
      (node (ref "COM4") (pin "7") (pinfunction "7_7") (pintype "passive"))
    )
    (net (code "141") (name "unconnected-(COM5-Pad7)") (class "Default")
      (node (ref "COM5") (pin "7") (pinfunction "7_7") (pintype "passive"))
    )
    (net (code "142") (name "unconnected-(COM6-Pad7)") (class "Default")
      (node (ref "COM6") (pin "7") (pinfunction "7_7") (pintype "passive"))
    )
    (net (code "143") (name "unconnected-(COM7-Pad7)") (class "Default")
      (node (ref "COM7") (pin "7") (pinfunction "7_7") (pintype "passive"))
    )
    (net (code "144") (name "unconnected-(DRIVE-Pad7)") (class "Default")
      (node (ref "DRIVE") (pin "7") (pinfunction "7_7") (pintype "passive"))
    )
    (net (code "145") (name "unconnected-(PWR-Pad1)") (class "Default")
      (node (ref "PWR") (pin "1") (pinfunction "1_1") (pintype "passive"))
    )
    (net (code "146") (name "unconnected-(PWR-Pad2)") (class "Default")
      (node (ref "PWR") (pin "2") (pinfunction "2_2") (pintype "passive"))
    )
    (net (code "147") (name "unconnected-(PWR-Pad6)") (class "Default")
      (node (ref "PWR") (pin "6") (pinfunction "6_6") (pintype "passive"))
    )
    (net (code "148") (name "unconnected-(SV1-Pad1)") (class "Default")
      (node (ref "SV1") (pin "1") (pinfunction "1_1") (pintype "passive"))
    )
    (net (code "149") (name "unconnected-(SV1-Pad4)") (class "Default")
      (node (ref "SV1") (pin "4") (pinfunction "4_4") (pintype "passive"))
    )
    (net (code "150") (name "unconnected-(SV1-Pad9)") (class "Default")
      (node (ref "SV1") (pin "9") (pinfunction "9_9") (pintype "passive"))
    )
    (net (code "151") (name "unconnected-(SV1-Pad12)") (class "Default")
      (node (ref "SV1") (pin "12") (pinfunction "12_12") (pintype "passive"))
    )
    (net (code "152") (name "unconnected-(SV1-Pad22)") (class "Default")
      (node (ref "SV1") (pin "22") (pinfunction "22_22") (pintype "passive"))
    )
    (net (code "153") (name "unconnected-(SV1-Pad23)") (class "Default")
      (node (ref "SV1") (pin "23") (pinfunction "23_23") (pintype "passive"))
    )
    (net (code "154") (name "unconnected-(SV1-Pad24)") (class "Default")
      (node (ref "SV1") (pin "24") (pinfunction "24_24") (pintype "passive"))
    )
    (net (code "155") (name "unconnected-(SV1-Pad25)") (class "Default")
      (node (ref "SV1") (pin "25") (pinfunction "25_25") (pintype "passive"))
    )
    (net (code "156") (name "unconnected-(SV1-Pad27)") (class "Default")
      (node (ref "SV1") (pin "27") (pinfunction "27_27") (pintype "passive"))
    )
    (net (code "157") (name "unconnected-(SV1-Pad29)") (class "Default")
      (node (ref "SV1") (pin "29") (pinfunction "29_29") (pintype "passive"))
    )
    (net (code "158") (name "unconnected-(SV1-Pad30)") (class "Default")
      (node (ref "SV1") (pin "30") (pinfunction "30_30") (pintype "passive"))
    )
    (net (code "159") (name "unconnected-(SV1-Pad32)") (class "Default")
      (node (ref "SV1") (pin "32") (pinfunction "32_32") (pintype "passive"))
    )
    (net (code "160") (name "unconnected-(SV1-Pad33)") (class "Default")
      (node (ref "SV1") (pin "33") (pinfunction "33_33") (pintype "passive"))
    )
    (net (code "161") (name "unconnected-(SV1-Pad37)") (class "Default")
      (node (ref "SV1") (pin "37") (pinfunction "37_37") (pintype "passive"))
    )
    (net (code "162") (name "unconnected-(SV1-Pad38)") (class "Default")
      (node (ref "SV1") (pin "38") (pinfunction "38_38") (pintype "passive"))
    )
    (net (code "163") (name "unconnected-(SV1-Pad39)") (class "Default")
      (node (ref "SV1") (pin "39") (pinfunction "39_39") (pintype "passive"))
    )
    (net (code "164") (name "unconnected-(SV1-Pad40)") (class "Default")
      (node (ref "SV1") (pin "40") (pinfunction "40_40") (pintype "passive"))
    )
    (net (code "165") (name "unconnected-(U$5-A8-PadP42)") (class "Default")
      (node (ref "U$5") (pin "P42") (pinfunction "A8_P42") (pintype "bidirectional"))
    )
    (net (code "166") (name "unconnected-(U$5-A9-PadP41)") (class "Default")
      (node (ref "U$5") (pin "P41") (pinfunction "A9_P41") (pintype "bidirectional"))
    )
    (net (code "167") (name "unconnected-(U$5-A11-PadP19)") (class "Default")
      (node (ref "U$5") (pin "P19") (pinfunction "A11_P19") (pintype "bidirectional"))
    )
    (net (code "168") (name "unconnected-(U$5-B8-PadP40)") (class "Default")
      (node (ref "U$5") (pin "P40") (pinfunction "B8_P40") (pintype "bidirectional"))
    )
    (net (code "169") (name "unconnected-(U$5-B9-PadP39)") (class "Default")
      (node (ref "U$5") (pin "P39") (pinfunction "B9_P39") (pintype "bidirectional"))
    )
    (net (code "170") (name "unconnected-(U$5-B11-PadP21)") (class "Default")
      (node (ref "U$5") (pin "P21") (pinfunction "B11_P21") (pintype "bidirectional"))
    )
    (net (code "171") (name "unconnected-(U$5-Y8-PadP3)") (class "Default")
      (node (ref "U$5") (pin "P3") (pinfunction "Y8_P3") (pintype "bidirectional"))
    )
    (net (code "172") (name "unconnected-(U$5-Y9-PadP4)") (class "Default")
      (node (ref "U$5") (pin "P4") (pinfunction "Y9_P4") (pintype "bidirectional"))
    )
    (net (code "173") (name "unconnected-(U$5-Y11-PadP14)") (class "Default")
      (node (ref "U$5") (pin "P14") (pinfunction "Y11_P14") (pintype "bidirectional"))
    )
    (net (code "174") (name "unconnected-(U$6-A8-PadP42)") (class "Default")
      (node (ref "U$6") (pin "P42") (pinfunction "A8_P42") (pintype "bidirectional"))
    )
    (net (code "175") (name "unconnected-(U$6-A9-PadP41)") (class "Default")
      (node (ref "U$6") (pin "P41") (pinfunction "A9_P41") (pintype "bidirectional"))
    )
    (net (code "176") (name "unconnected-(U$6-A10-PadP18)") (class "Default")
      (node (ref "U$6") (pin "P18") (pinfunction "A10_P18") (pintype "bidirectional"))
    )
    (net (code "177") (name "unconnected-(U$6-A11-PadP19)") (class "Default")
      (node (ref "U$6") (pin "P19") (pinfunction "A11_P19") (pintype "bidirectional"))
    )
    (net (code "178") (name "unconnected-(U$6-B8-PadP40)") (class "Default")
      (node (ref "U$6") (pin "P40") (pinfunction "B8_P40") (pintype "bidirectional"))
    )
    (net (code "179") (name "unconnected-(U$6-B9-PadP39)") (class "Default")
      (node (ref "U$6") (pin "P39") (pinfunction "B9_P39") (pintype "bidirectional"))
    )
    (net (code "180") (name "unconnected-(U$6-B10-PadP20)") (class "Default")
      (node (ref "U$6") (pin "P20") (pinfunction "B10_P20") (pintype "bidirectional"))
    )
    (net (code "181") (name "unconnected-(U$6-B11-PadP21)") (class "Default")
      (node (ref "U$6") (pin "P21") (pinfunction "B11_P21") (pintype "bidirectional"))
    )
    (net (code "182") (name "unconnected-(U$6-Y8-PadP3)") (class "Default")
      (node (ref "U$6") (pin "P3") (pinfunction "Y8_P3") (pintype "bidirectional"))
    )
    (net (code "183") (name "unconnected-(U$6-Y9-PadP4)") (class "Default")
      (node (ref "U$6") (pin "P4") (pinfunction "Y9_P4") (pintype "bidirectional"))
    )
    (net (code "184") (name "unconnected-(U$6-Y10-PadP15)") (class "Default")
      (node (ref "U$6") (pin "P15") (pinfunction "Y10_P15") (pintype "bidirectional"))
    )
    (net (code "185") (name "unconnected-(U$6-Y11-PadP14)") (class "Default")
      (node (ref "U$6") (pin "P14") (pinfunction "Y11_P14") (pintype "bidirectional"))
    )
    (net (code "186") (name "unconnected-(U1-0(RX0)-Pad0)") (class "Default")
      (node (ref "U1") (pin "0") (pinfunction "0(RX0)_0") (pintype "bidirectional"))
    )
    (net (code "187") (name "unconnected-(U1-1(TX0)-Pad1)") (class "Default")
      (node (ref "U1") (pin "1") (pinfunction "1(TX0)_1") (pintype "bidirectional"))
    )
    (net (code "188") (name "unconnected-(U1-5V-Pad5V@0)") (class "Default")
      (node (ref "U1") (pin "5V@0") (pinfunction "5V_5V@0") (pintype "bidirectional"))
    )
    (net (code "189") (name "unconnected-(U1-5V-Pad5V@1)") (class "Default")
      (node (ref "U1") (pin "5V@1") (pinfunction "5V_5V@1") (pintype "bidirectional"))
    )
    (net (code "190") (name "unconnected-(U1-5V-Pad5V@2)") (class "Default")
      (node (ref "U1") (pin "5V@2") (pinfunction "5V_5V@2") (pintype "bidirectional"))
    )
    (net (code "191") (name "unconnected-(U1-14(TX3)-Pad14)") (class "Default")
      (node (ref "U1") (pin "14") (pinfunction "14(TX3)_14") (pintype "bidirectional"))
    )
    (net (code "192") (name "unconnected-(U1-15(RX3)-Pad15)") (class "Default")
      (node (ref "U1") (pin "15") (pinfunction "15(RX3)_15") (pintype "bidirectional"))
    )
    (net (code "193") (name "unconnected-(U1-16(TX2)-Pad16)") (class "Default")
      (node (ref "U1") (pin "16") (pinfunction "16(TX2)_16") (pintype "bidirectional"))
    )
    (net (code "194") (name "unconnected-(U1-17(RX2)-Pad17)") (class "Default")
      (node (ref "U1") (pin "17") (pinfunction "17(RX2)_17") (pintype "bidirectional"))
    )
    (net (code "195") (name "unconnected-(U1-18(TX1)-Pad18)") (class "Default")
      (node (ref "U1") (pin "18") (pinfunction "18(TX1)_18") (pintype "bidirectional"))
    )
    (net (code "196") (name "unconnected-(U1-19(RX1)-Pad19)") (class "Default")
      (node (ref "U1") (pin "19") (pinfunction "19(RX1)_19") (pintype "bidirectional"))
    )
    (net (code "197") (name "unconnected-(U1-20(SDA)-Pad20)") (class "Default")
      (node (ref "U1") (pin "20") (pinfunction "20(SDA)_20") (pintype "bidirectional"))
    )
    (net (code "198") (name "unconnected-(U1-21(SCL)-Pad21)") (class "Default")
      (node (ref "U1") (pin "21") (pinfunction "21(SCL)_21") (pintype "bidirectional"))
    )
    (net (code "199") (name "unconnected-(U1-A0(RX0)-PadA0)") (class "Default")
      (node (ref "U1") (pin "A0") (pinfunction "A0(RX0)_A0") (pintype "bidirectional"))
    )
    (net (code "200") (name "unconnected-(U1-A1(TX0)-PadA1)") (class "Default")
      (node (ref "U1") (pin "A1") (pinfunction "A1(TX0)_A1") (pintype "bidirectional"))
    )
    (net (code "201") (name "unconnected-(U1-GND-PadGND@0)") (class "Default")
      (node (ref "U1") (pin "GND@0") (pinfunction "GND_GND@0") (pintype "bidirectional"))
    )
    (net (code "202") (name "unconnected-(U1-GND-PadGND@1)") (class "Default")
      (node (ref "U1") (pin "GND@1") (pinfunction "GND_GND@1") (pintype "bidirectional"))
    )
    (net (code "203") (name "unconnected-(U1-GND-PadGND@2)") (class "Default")
      (node (ref "U1") (pin "GND@2") (pinfunction "GND_GND@2") (pintype "bidirectional"))
    )
    (net (code "204") (name "unconnected-(U1-GND-PadGND@3)") (class "Default")
      (node (ref "U1") (pin "GND@3") (pinfunction "GND_GND@3") (pintype "bidirectional"))
    )
    (net (code "205") (name "unconnected-(U1-GND-PadGND@4)") (class "Default")
      (node (ref "U1") (pin "GND@4") (pinfunction "GND_GND@4") (pintype "bidirectional"))
    )
    (net (code "206") (name "unconnected-(U1-Pad2)") (class "Default")
      (node (ref "U1") (pin "2") (pinfunction "2_2") (pintype "bidirectional"))
    )
    (net (code "207") (name "unconnected-(U1-Pad3)") (class "Default")
      (node (ref "U1") (pin "3") (pinfunction "3_3") (pintype "bidirectional"))
    )
    (net (code "208") (name "unconnected-(U1-Pad3.3V)") (class "Default")
      (node (ref "U1") (pin "3.3V") (pinfunction "3.3V_3.3V") (pintype "bidirectional"))
    )
    (net (code "209") (name "unconnected-(U1-Pad4)") (class "Default")
      (node (ref "U1") (pin "4") (pinfunction "4_4") (pintype "bidirectional"))
    )
    (net (code "210") (name "unconnected-(U1-Pad5)") (class "Default")
      (node (ref "U1") (pin "5") (pinfunction "5_5") (pintype "bidirectional"))
    )
    (net (code "211") (name "unconnected-(U1-Pad6)") (class "Default")
      (node (ref "U1") (pin "6") (pinfunction "6_6") (pintype "bidirectional"))
    )
    (net (code "212") (name "unconnected-(U1-Pad7)") (class "Default")
      (node (ref "U1") (pin "7") (pinfunction "7_7") (pintype "bidirectional"))
    )
    (net (code "213") (name "unconnected-(U1-Pad8)") (class "Default")
      (node (ref "U1") (pin "8") (pinfunction "8_8") (pintype "bidirectional"))
    )
    (net (code "214") (name "unconnected-(U1-Pad9)") (class "Default")
      (node (ref "U1") (pin "9") (pinfunction "9_9") (pintype "bidirectional"))
    )
    (net (code "215") (name "unconnected-(U1-Pad10)") (class "Default")
      (node (ref "U1") (pin "10") (pinfunction "10_10") (pintype "bidirectional"))
    )
    (net (code "216") (name "unconnected-(U1-Pad11)") (class "Default")
      (node (ref "U1") (pin "11") (pinfunction "11_11") (pintype "bidirectional"))
    )
    (net (code "217") (name "unconnected-(U1-Pad12)") (class "Default")
      (node (ref "U1") (pin "12") (pinfunction "12_12") (pintype "bidirectional"))
    )
    (net (code "218") (name "unconnected-(U1-Pad13)") (class "Default")
      (node (ref "U1") (pin "13") (pinfunction "13_13") (pintype "bidirectional"))
    )
    (net (code "219") (name "unconnected-(U1-Pad22)") (class "Default")
      (node (ref "U1") (pin "22") (pinfunction "22_22") (pintype "bidirectional"))
    )
    (net (code "220") (name "unconnected-(U1-Pad23)") (class "Default")
      (node (ref "U1") (pin "23") (pinfunction "23_23") (pintype "bidirectional"))
    )
    (net (code "221") (name "unconnected-(U1-Pad24)") (class "Default")
      (node (ref "U1") (pin "24") (pinfunction "24_24") (pintype "bidirectional"))
    )
    (net (code "222") (name "unconnected-(U1-Pad25)") (class "Default")
      (node (ref "U1") (pin "25") (pinfunction "25_25") (pintype "bidirectional"))
    )
    (net (code "223") (name "unconnected-(U1-Pad26)") (class "Default")
      (node (ref "U1") (pin "26") (pinfunction "26_26") (pintype "bidirectional"))
    )
    (net (code "224") (name "unconnected-(U1-Pad27)") (class "Default")
      (node (ref "U1") (pin "27") (pinfunction "27_27") (pintype "bidirectional"))
    )
    (net (code "225") (name "unconnected-(U1-Pad28)") (class "Default")
      (node (ref "U1") (pin "28") (pinfunction "28_28") (pintype "bidirectional"))
    )
    (net (code "226") (name "unconnected-(U1-Pad29)") (class "Default")
      (node (ref "U1") (pin "29") (pinfunction "29_29") (pintype "bidirectional"))
    )
    (net (code "227") (name "unconnected-(U1-Pad30)") (class "Default")
      (node (ref "U1") (pin "30") (pinfunction "30_30") (pintype "bidirectional"))
    )
    (net (code "228") (name "unconnected-(U1-Pad31)") (class "Default")
      (node (ref "U1") (pin "31") (pinfunction "31_31") (pintype "bidirectional"))
    )
    (net (code "229") (name "unconnected-(U1-Pad32)") (class "Default")
      (node (ref "U1") (pin "32") (pinfunction "32_32") (pintype "bidirectional"))
    )
    (net (code "230") (name "unconnected-(U1-Pad33)") (class "Default")
      (node (ref "U1") (pin "33") (pinfunction "33_33") (pintype "bidirectional"))
    )
    (net (code "231") (name "unconnected-(U1-Pad34)") (class "Default")
      (node (ref "U1") (pin "34") (pinfunction "34_34") (pintype "bidirectional"))
    )
    (net (code "232") (name "unconnected-(U1-Pad35)") (class "Default")
      (node (ref "U1") (pin "35") (pinfunction "35_35") (pintype "bidirectional"))
    )
    (net (code "233") (name "unconnected-(U1-Pad36)") (class "Default")
      (node (ref "U1") (pin "36") (pinfunction "36_36") (pintype "bidirectional"))
    )
    (net (code "234") (name "unconnected-(U1-Pad37)") (class "Default")
      (node (ref "U1") (pin "37") (pinfunction "37_37") (pintype "bidirectional"))
    )
    (net (code "235") (name "unconnected-(U1-Pad38)") (class "Default")
      (node (ref "U1") (pin "38") (pinfunction "38_38") (pintype "bidirectional"))
    )
    (net (code "236") (name "unconnected-(U1-Pad39)") (class "Default")
      (node (ref "U1") (pin "39") (pinfunction "39_39") (pintype "bidirectional"))
    )
    (net (code "237") (name "unconnected-(U1-Pad40)") (class "Default")
      (node (ref "U1") (pin "40") (pinfunction "40_40") (pintype "bidirectional"))
    )
    (net (code "238") (name "unconnected-(U1-Pad41)") (class "Default")
      (node (ref "U1") (pin "41") (pinfunction "41_41") (pintype "bidirectional"))
    )
    (net (code "239") (name "unconnected-(U1-Pad42)") (class "Default")
      (node (ref "U1") (pin "42") (pinfunction "42_42") (pintype "bidirectional"))
    )
    (net (code "240") (name "unconnected-(U1-Pad43)") (class "Default")
      (node (ref "U1") (pin "43") (pinfunction "43_43") (pintype "bidirectional"))
    )
    (net (code "241") (name "unconnected-(U1-Pad44)") (class "Default")
      (node (ref "U1") (pin "44") (pinfunction "44_44") (pintype "bidirectional"))
    )
    (net (code "242") (name "unconnected-(U1-Pad45)") (class "Default")
      (node (ref "U1") (pin "45") (pinfunction "45_45") (pintype "bidirectional"))
    )
    (net (code "243") (name "unconnected-(U1-Pad46)") (class "Default")
      (node (ref "U1") (pin "46") (pinfunction "46_46") (pintype "bidirectional"))
    )
    (net (code "244") (name "unconnected-(U1-Pad47)") (class "Default")
      (node (ref "U1") (pin "47") (pinfunction "47_47") (pintype "bidirectional"))
    )
    (net (code "245") (name "unconnected-(U1-Pad48)") (class "Default")
      (node (ref "U1") (pin "48") (pinfunction "48_48") (pintype "bidirectional"))
    )
    (net (code "246") (name "unconnected-(U1-Pad49)") (class "Default")
      (node (ref "U1") (pin "49") (pinfunction "49_49") (pintype "bidirectional"))
    )
    (net (code "247") (name "unconnected-(U1-Pad50)") (class "Default")
      (node (ref "U1") (pin "50") (pinfunction "50_50") (pintype "bidirectional"))
    )
    (net (code "248") (name "unconnected-(U1-Pad51)") (class "Default")
      (node (ref "U1") (pin "51") (pinfunction "51_51") (pintype "bidirectional"))
    )
    (net (code "249") (name "unconnected-(U1-Pad52)") (class "Default")
      (node (ref "U1") (pin "52") (pinfunction "52_52") (pintype "bidirectional"))
    )
    (net (code "250") (name "unconnected-(U1-Pad53)") (class "Default")
      (node (ref "U1") (pin "53") (pinfunction "53_53") (pintype "bidirectional"))
    )
    (net (code "251") (name "unconnected-(U1-PadA2)") (class "Default")
      (node (ref "U1") (pin "A2") (pinfunction "A2_A2") (pintype "bidirectional"))
    )
    (net (code "252") (name "unconnected-(U1-PadA3)") (class "Default")
      (node (ref "U1") (pin "A3") (pinfunction "A3_A3") (pintype "bidirectional"))
    )
    (net (code "253") (name "unconnected-(U1-PadA4)") (class "Default")
      (node (ref "U1") (pin "A4") (pinfunction "A4_A4") (pintype "bidirectional"))
    )
    (net (code "254") (name "unconnected-(U1-PadA5)") (class "Default")
      (node (ref "U1") (pin "A5") (pinfunction "A5_A5") (pintype "bidirectional"))
    )
    (net (code "255") (name "unconnected-(U1-PadA6)") (class "Default")
      (node (ref "U1") (pin "A6") (pinfunction "A6_A6") (pintype "bidirectional"))
    )
    (net (code "256") (name "unconnected-(U1-PadA7)") (class "Default")
      (node (ref "U1") (pin "A7") (pinfunction "A7_A7") (pintype "bidirectional"))
    )
    (net (code "257") (name "unconnected-(U1-PadA8)") (class "Default")
      (node (ref "U1") (pin "A8") (pinfunction "A8_A8") (pintype "bidirectional"))
    )
    (net (code "258") (name "unconnected-(U1-PadA9)") (class "Default")
      (node (ref "U1") (pin "A9") (pinfunction "A9_A9") (pintype "bidirectional"))
    )
    (net (code "259") (name "unconnected-(U1-PadA10)") (class "Default")
      (node (ref "U1") (pin "A10") (pinfunction "A10_A10") (pintype "bidirectional"))
    )
    (net (code "260") (name "unconnected-(U1-PadA11)") (class "Default")
      (node (ref "U1") (pin "A11") (pinfunction "A11_A11") (pintype "bidirectional"))
    )
    (net (code "261") (name "unconnected-(U1-PadA12)") (class "Default")
      (node (ref "U1") (pin "A12") (pinfunction "A12_A12") (pintype "bidirectional"))
    )
    (net (code "262") (name "unconnected-(U1-PadA13)") (class "Default")
      (node (ref "U1") (pin "A13") (pinfunction "A13_A13") (pintype "bidirectional"))
    )
    (net (code "263") (name "unconnected-(U1-PadA14)") (class "Default")
      (node (ref "U1") (pin "A14") (pinfunction "A14_A14") (pintype "bidirectional"))
    )
    (net (code "264") (name "unconnected-(U1-PadA15)") (class "Default")
      (node (ref "U1") (pin "A15") (pinfunction "A15_A15") (pintype "bidirectional"))
    )
    (net (code "265") (name "unconnected-(U1-PadAREF)") (class "Default")
      (node (ref "U1") (pin "AREF") (pinfunction "AREF_AREF") (pintype "bidirectional"))
    )
    (net (code "266") (name "unconnected-(U1-PadRESET)") (class "Default")
      (node (ref "U1") (pin "RESET") (pinfunction "RESET_RESET") (pintype "bidirectional"))
    )
    (net (code "267") (name "unconnected-(U1-PadVIN)") (class "Default")
      (node (ref "U1") (pin "VIN") (pinfunction "VIN_VIN") (pintype "bidirectional"))
    )
    (net (code "268") (name "unconnected-(X1B-DATA1+-Pad10)") (class "Default")
      (node (ref "X1") (pin "10") (pinfunction "DATA1+_10") (pintype "passive"))
    )
    (net (code "269") (name "unconnected-(X1B-DATA1--Pad9)") (class "Default")
      (node (ref "X1") (pin "9") (pinfunction "DATA1-_9") (pintype "passive"))
    )
  )
)
